# 2022_EDA.net
KiCad netlist of a schematic drawn in EasyEDA Pro
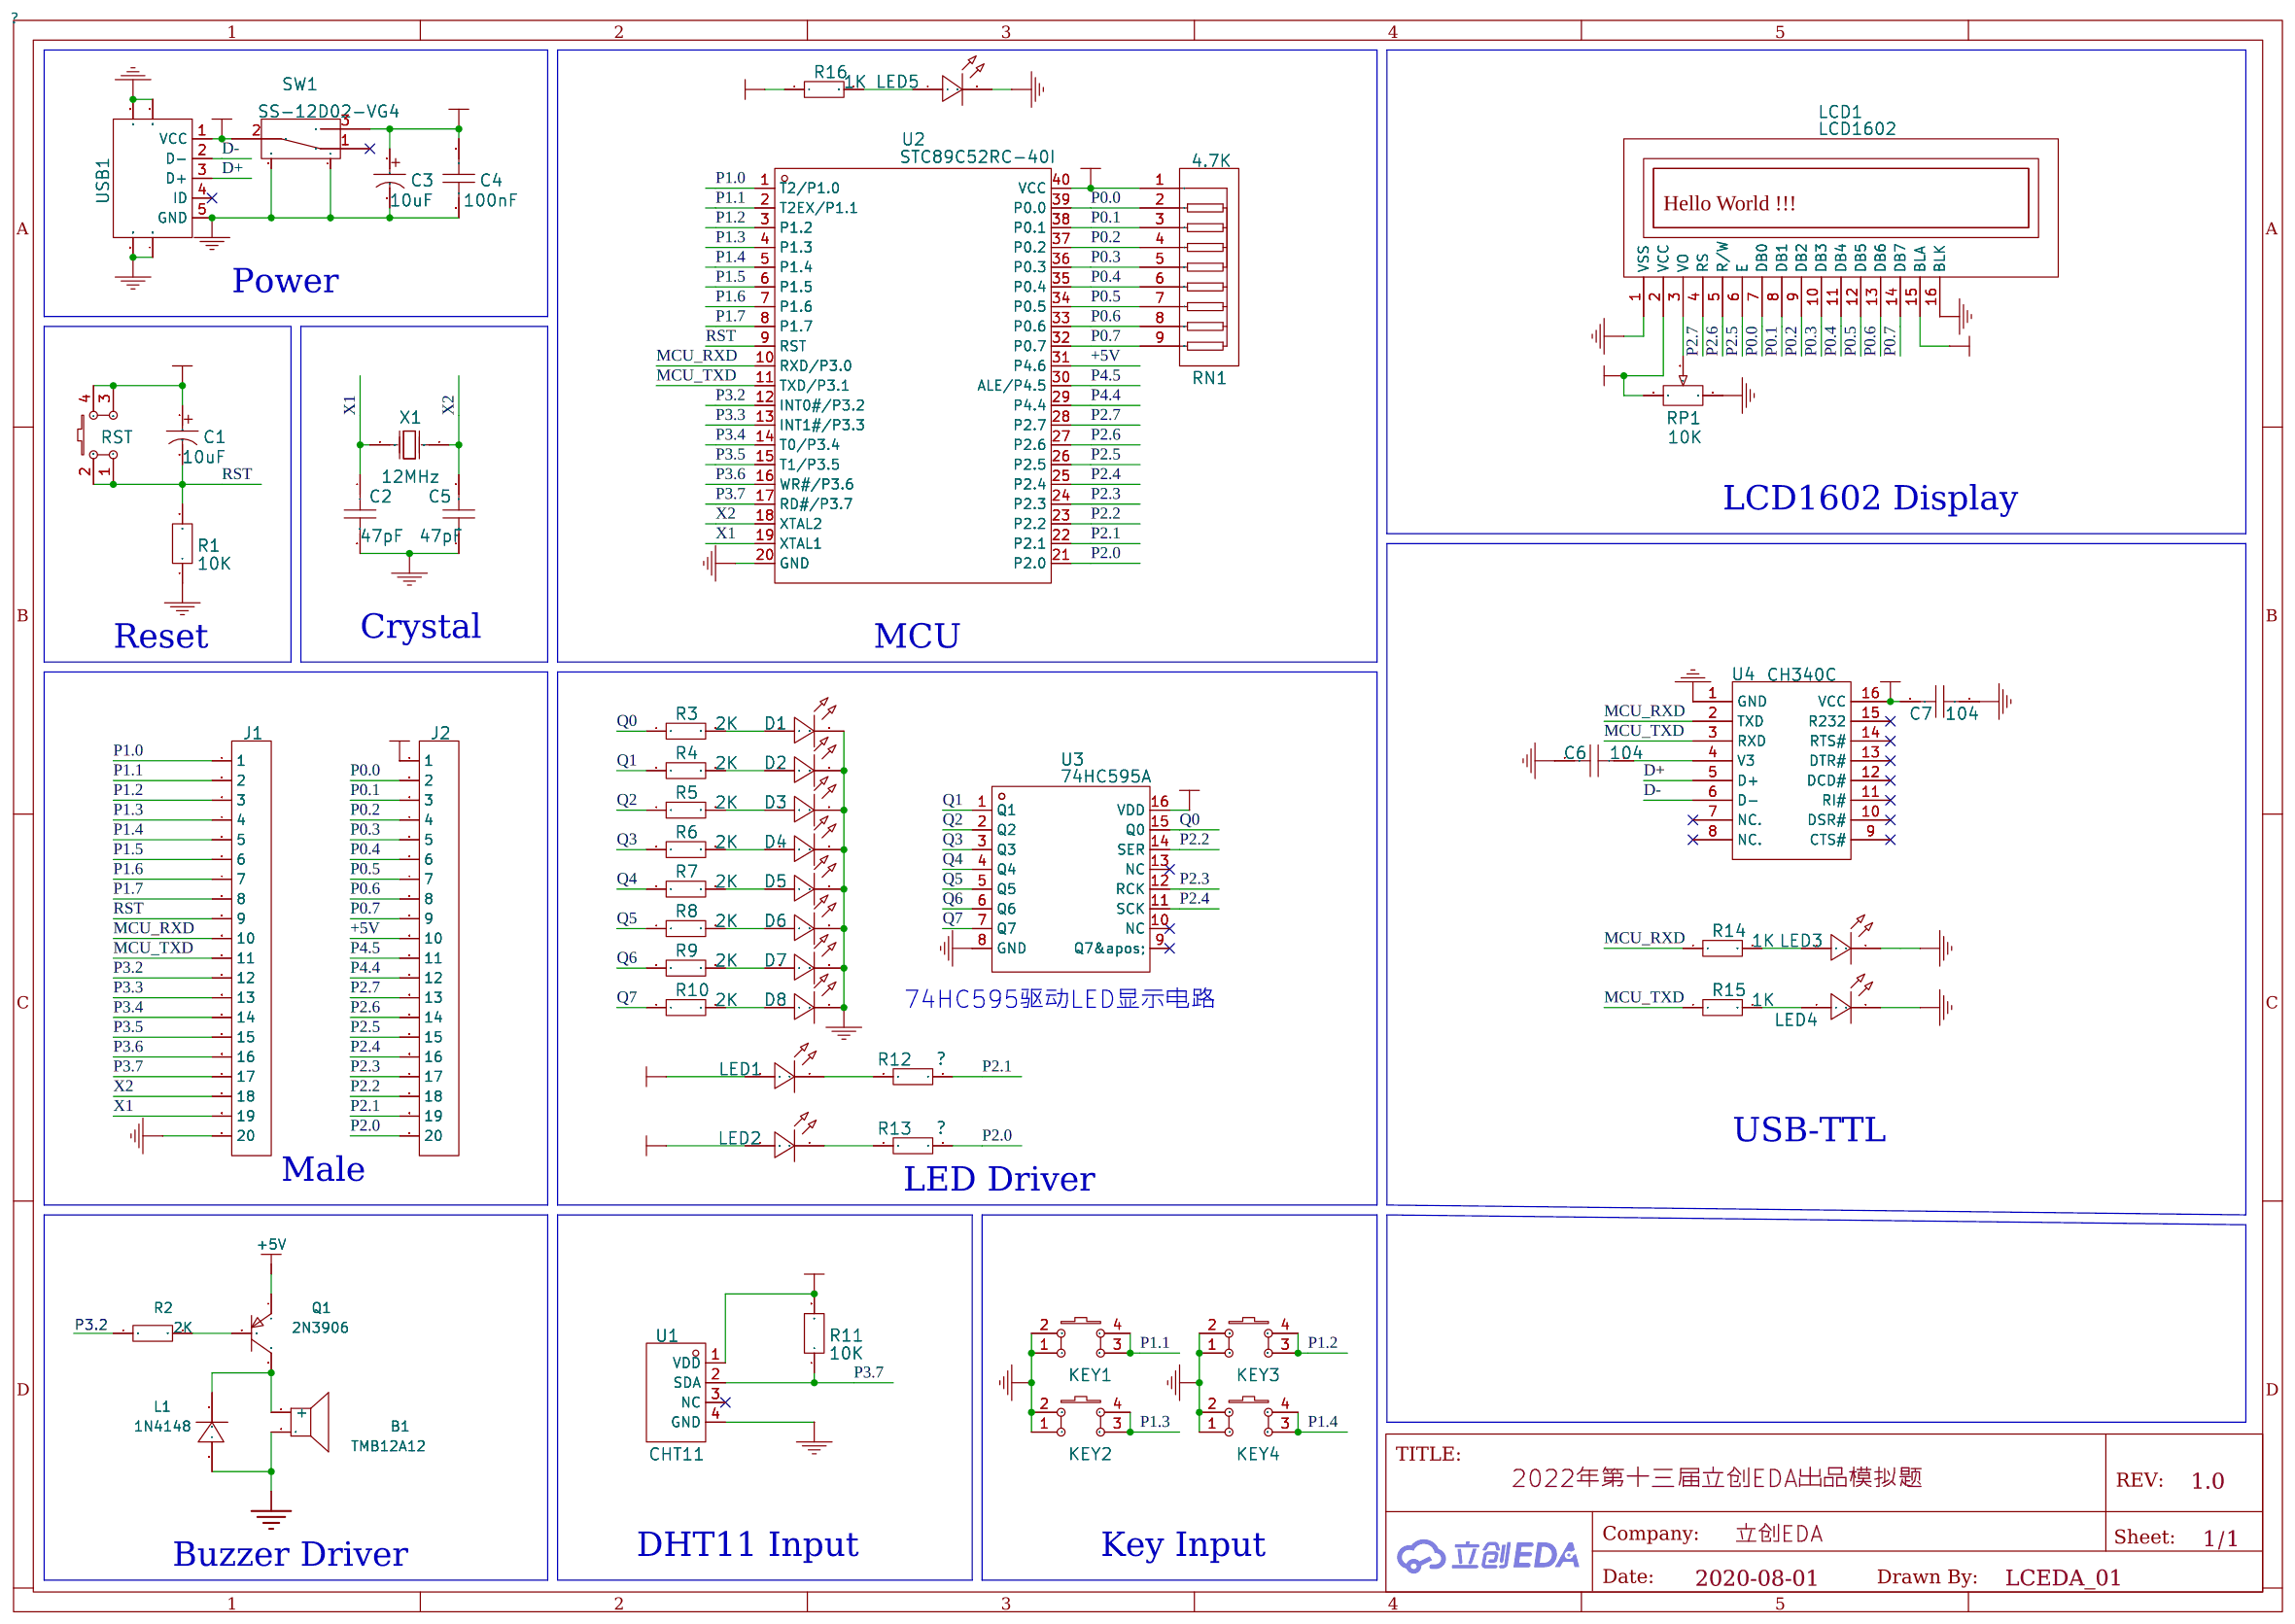
[diagram p0: schematic sheet]

(export (version "E")
  (design (tool "Eeschema 10.0.6"))
  (components
    (comp (ref "B1") (value "TMB12A12") (libsource (lib "easyedapro") (part "TMB12A12")))
    (comp (ref "C1")
      (value "10uF")
      (fields (field (name "Manufacturer Part") "10uF 25V 5*11") (field (name "Manufacturer") "ValuePro"))
      (libsource (lib "easyedapro") (part "10uF"))
    )
    (comp (ref "C2")
      (value "47pF")
      (fields
        (field (name "Manufacturer Part") "CC81-N5S2L1B470KSE")
        (field (name "Manufacturer") "Guangdong Fenghua Advanced Tech")
      )
      (libsource (lib "easyedapro") (part "47pF"))
    )
    (comp (ref "C3")
      (value "10uF")
      (fields (field (name "Manufacturer Part") "10uF 25V 5*11") (field (name "Manufacturer") "ValuePro"))
      (libsource (lib "easyedapro") (part "10uF"))
    )
    (comp (ref "C4")
      (value "100nF")
      (fields
        (field (name "Manufacturer Part") "CC1H104ZA1FD3F5O10MF")
        (field (name "Manufacturer") "Dersonic")
      )
      (libsource (lib "easyedapro") (part "104"))
    )
    (comp (ref "C5")
      (value "47pF")
      (fields
        (field (name "Manufacturer Part") "CC81-N5S2L1B470KSE")
        (field (name "Manufacturer") "Guangdong Fenghua Advanced Tech")
      )
      (libsource (lib "easyedapro") (part "47pF"))
    )
    (comp (ref "C6")
      (value "104")
      (fields
        (field (name "Manufacturer Part") "CC1H104ZA1FD3F5O10MF")
        (field (name "Manufacturer") "Dersonic")
      )
      (libsource (lib "easyedapro") (part "104"))
    )
    (comp (ref "C7")
      (value "104")
      (fields
        (field (name "Manufacturer Part") "CC1H104ZA1FD3F5O10MF")
        (field (name "Manufacturer") "Dersonic")
      )
      (libsource (lib "easyedapro") (part "104"))
    )
    (comp (ref "D1")
      (value "LED-0805_B")
      (fields (field (name "Manufacturer Part") "D-B080508B1-KS2") (field (name "Manufacturer") "方舟 ARKLED"))
      (libsource (lib "easyedapro") (part "LED-0805_B"))
    )
    (comp (ref "D2")
      (value "LED-0805_B")
      (fields (field (name "Manufacturer Part") "D-B080508B1-KS2") (field (name "Manufacturer") "方舟 ARKLED"))
      (libsource (lib "easyedapro") (part "LED-0805_B"))
    )
    (comp (ref "D3")
      (value "LED-0805_B")
      (fields (field (name "Manufacturer Part") "D-B080508B1-KS2") (field (name "Manufacturer") "方舟 ARKLED"))
      (libsource (lib "easyedapro") (part "LED-0805_B"))
    )
    (comp (ref "D4")
      (value "LED-0805_B")
      (fields (field (name "Manufacturer Part") "D-B080508B1-KS2") (field (name "Manufacturer") "方舟 ARKLED"))
      (libsource (lib "easyedapro") (part "LED-0805_B"))
    )
    (comp (ref "D5")
      (value "LED-0805_B")
      (fields (field (name "Manufacturer Part") "D-B080508B1-KS2") (field (name "Manufacturer") "方舟 ARKLED"))
      (libsource (lib "easyedapro") (part "LED-0805_B"))
    )
    (comp (ref "D6")
      (value "LED-0805_B")
      (fields (field (name "Manufacturer Part") "D-B080508B1-KS2") (field (name "Manufacturer") "方舟 ARKLED"))
      (libsource (lib "easyedapro") (part "LED-0805_B"))
    )
    (comp (ref "D7")
      (value "LED-0805_B")
      (fields (field (name "Manufacturer Part") "D-B080508B1-KS2") (field (name "Manufacturer") "方舟 ARKLED"))
      (libsource (lib "easyedapro") (part "LED-0805_B"))
    )
    (comp (ref "D8")
      (value "LED-0805_B")
      (fields (field (name "Manufacturer Part") "D-B080508B1-KS2") (field (name "Manufacturer") "方舟 ARKLED"))
      (libsource (lib "easyedapro") (part "LED-0805_B"))
    )
    (comp (ref "J1") (value "HDR-M-2.54_1x20") (libsource (lib "easyedapro") (part "HDR-M-2.54_1x20")))
    (comp (ref "J2") (value "HDR-M-2.54_1x20") (libsource (lib "easyedapro") (part "HDR-M-2.54_1x20")))
    (comp (ref "KEY1")
      (value "K4-6×6_SMD")
      (fields (field (name "Manufacturer Part") "K2-6639SP-D4SC-04") (field (name "Manufacturer") "韩国韩荣"))
      (libsource (lib "easyedapro") (part "K4-6×6_SMD"))
    )
    (comp (ref "KEY2")
      (value "K4-6×6_SMD")
      (fields (field (name "Manufacturer Part") "K2-6639SP-D4SC-04") (field (name "Manufacturer") "韩国韩荣"))
      (libsource (lib "easyedapro") (part "K4-6×6_SMD"))
    )
    (comp (ref "KEY3")
      (value "K4-6×6_SMD")
      (fields (field (name "Manufacturer Part") "K2-6639SP-D4SC-04") (field (name "Manufacturer") "韩国韩荣"))
      (libsource (lib "easyedapro") (part "K4-6×6_SMD"))
    )
    (comp (ref "KEY4")
      (value "K4-6×6_SMD")
      (fields (field (name "Manufacturer Part") "K2-6639SP-D4SC-04") (field (name "Manufacturer") "韩国韩荣"))
      (libsource (lib "easyedapro") (part "K4-6×6_SMD"))
    )
    (comp (ref "L1") (value "1N4148") (libsource (lib "easyedapro") (part "1N4148")))
    (comp (ref "LCD1")
      (value "LCD1602")
      (fields
        (field (name "Manufacturer Part") "LCM1602K-NSW-BBW")
        (field (name "Manufacturer") "LONTECH(厦门龙特)")
      )
      (libsource (lib "easyedapro") (part "LCD1602"))
    )
    (comp (ref "LED1")
      (value "LED-TH-3mm_B")
      (fields
        (field (name "Manufacturer Part") "204-10SUBC/S400-A4")
        (field (name "Manufacturer") "EVERLIGHT(台湾亿光)")
      )
      (libsource (lib "easyedapro") (part "LED-TH-3mm_B"))
    )
    (comp (ref "LED2")
      (value "LED-TH-3mm_G")
      (fields
        (field (name "Manufacturer Part") "204-10SYGD/S530-E3")
        (field (name "Manufacturer") "EVERLIGHT(台湾亿光)")
      )
      (libsource (lib "easyedapro") (part "LED-TH-3mm_G"))
    )
    (comp (ref "LED3")
      (value "LED-0805_B")
      (fields (field (name "Manufacturer Part") "D-B080508B1-KS2") (field (name "Manufacturer") "方舟 ARKLED"))
      (libsource (lib "easyedapro") (part "LED-0805_B"))
    )
    (comp (ref "LED4")
      (value "LED-0805_G")
      (fields (field (name "Manufacturer Part") "NCD0805G1") (field (name "Manufacturer") "国星光电"))
      (libsource (lib "easyedapro") (part "LED-0805_G"))
    )
    (comp (ref "LED5")
      (value "LED-TH-3mm_R")
      (fields
        (field (name "Manufacturer Part") "204-10SDRD/S530-A3-L")
        (field (name "Manufacturer") "EVERLIGHT(台湾亿光)")
      )
      (libsource (lib "easyedapro") (part "LED-TH-3mm_R"))
    )
    (comp (ref "Q1") (value "2N3906") (libsource (lib "easyedapro") (part "2N3906")))
    (comp (ref "R1")
      (value "10K")
      (fields (field (name "Manufacturer Part") "RN 1/4W 10K F T/B A1") (field (name "Manufacturer") "TyoHM"))
      (libsource (lib "") (part "10K_1"))
    )
    (comp (ref "R2") (value "2K") (libsource (lib "") (part "2K_1")))
    (comp (ref "R3")
      (value "2K")
      (fields (field (name "Manufacturer Part") "ARG05FTC2001") (field (name "Manufacturer") "Viking Tech"))
      (libsource (lib "easyedapro") (part "2K"))
    )
    (comp (ref "R4")
      (value "2K")
      (fields (field (name "Manufacturer Part") "ARG05FTC2001") (field (name "Manufacturer") "Viking Tech"))
      (libsource (lib "easyedapro") (part "2K"))
    )
    (comp (ref "R5")
      (value "2K")
      (fields (field (name "Manufacturer Part") "ARG05FTC2001") (field (name "Manufacturer") "Viking Tech"))
      (libsource (lib "easyedapro") (part "2K"))
    )
    (comp (ref "R6")
      (value "2K")
      (fields (field (name "Manufacturer Part") "ARG05FTC2001") (field (name "Manufacturer") "Viking Tech"))
      (libsource (lib "easyedapro") (part "2K"))
    )
    (comp (ref "R7")
      (value "2K")
      (fields (field (name "Manufacturer Part") "ARG05FTC2001") (field (name "Manufacturer") "Viking Tech"))
      (libsource (lib "easyedapro") (part "2K"))
    )
    (comp (ref "R8")
      (value "2K")
      (fields (field (name "Manufacturer Part") "ARG05FTC2001") (field (name "Manufacturer") "Viking Tech"))
      (libsource (lib "easyedapro") (part "2K"))
    )
    (comp (ref "R9")
      (value "2K")
      (fields (field (name "Manufacturer Part") "ARG05FTC2001") (field (name "Manufacturer") "Viking Tech"))
      (libsource (lib "easyedapro") (part "2K"))
    )
    (comp (ref "R10")
      (value "2K")
      (fields (field (name "Manufacturer Part") "ARG05FTC2001") (field (name "Manufacturer") "Viking Tech"))
      (libsource (lib "easyedapro") (part "2K"))
    )
    (comp (ref "R11")
      (value "10K")
      (fields (field (name "Manufacturer Part") "RN 1/4W 10K F T/B A1") (field (name "Manufacturer") "TyoHM"))
      (libsource (lib "") (part "10K_1"))
    )
    (comp (ref "R12")
      (value "？")
      (fields (field (name "Manufacturer Part") "RN1/2WS2KΩFT/BA1") (field (name "Manufacturer") "TyoHM"))
      (libsource (lib "easyedapro") (part "？"))
    )
    (comp (ref "R13")
      (value "？")
      (fields (field (name "Manufacturer Part") "RN1/2WS2KΩFT/BA1") (field (name "Manufacturer") "TyoHM"))
      (libsource (lib "easyedapro") (part "？"))
    )
    (comp (ref "R14")
      (value "1K")
      (fields (field (name "Manufacturer Part") "ARG05FTC2001") (field (name "Manufacturer") "Viking Tech"))
      (libsource (lib "easyedapro") (part "2K"))
    )
    (comp (ref "R15")
      (value "1K")
      (fields (field (name "Manufacturer Part") "ARG05FTC2001") (field (name "Manufacturer") "Viking Tech"))
      (libsource (lib "easyedapro") (part "2K"))
    )
    (comp (ref "R16")
      (value "1K")
      (fields (field (name "Manufacturer Part") "RN1/2WS2KΩFT/BA1") (field (name "Manufacturer") "TyoHM"))
      (libsource (lib "easyedapro") (part "？"))
    )
    (comp (ref "RN1")
      (value "4.7K")
      (fields (field (name "Manufacturer Part") "A09-472JP") (field (name "Manufacturer") "FH"))
      (libsource (lib "easyedapro") (part "4.7K"))
    )
    (comp (ref "RP1") (value "10K") (libsource (lib "easyedapro") (part "10K")))
    (comp (ref "RST")
      (value "K4-6×6_SMD")
      (fields (field (name "Manufacturer Part") "K2-6639SP-D4SC-04") (field (name "Manufacturer") "韩国韩荣"))
      (libsource (lib "easyedapro") (part "K4-6×6_SMD"))
    )
    (comp (ref "SW1")
      (value "SS-12D02-VG4")
      (fields (field (name "Manufacturer") "Rectangular Connectors - Contacts"))
      (libsource (lib "easyedapro") (part "SS-12D02-VG4"))
    )
    (comp (ref "U1")
      (value "CHT11")
      (fields (field (name "Manufacturer") "CYBERSEN"))
      (libsource (lib "easyedapro") (part "CHT11"))
    )
    (comp (ref "U2")
      (value "STC89C52RC-40I")
      (fields (field (name "Manufacturer") "STC"))
      (libsource (lib "easyedapro") (part "STC89C52RC-40I"))
    )
    (comp (ref "U3")
      (value "74HC595A")
      (fields (field (name "Manufacturer") "FM"))
      (libsource (lib "easyedapro") (part "74HC595A"))
    )
    (comp (ref "U4")
      (value "CH340C")
      (fields (field (name "Manufacturer") "WCH"))
      (libsource (lib "easyedapro") (part "CH340C"))
    )
    (comp (ref "USB1")
      (value "USB-Micro_2")
      (fields (field (name "Manufacturer") "ValuePro"))
      (libsource (lib "easyedapro") (part "USB-Micro_2"))
    )
    (comp (ref "X1")
      (value "12MHz")
      (fields
        (field (name "Manufacturer Part") "B12000J233")
        (field (name "Manufacturer") "ZheJiang East Crystal Elec")
      )
      (libsource (lib "easyedapro") (part "12MHz"))
    )
  )
  (nets
    (net (code "1") (name "+5V") (class "Default")
      (node (ref "C1") (pin "1") (pinfunction "1_1") (pintype "input"))
      (node (ref "C3") (pin "1") (pinfunction "1_1") (pintype "input"))
      (node (ref "C4") (pin "2") (pinfunction "2_2") (pintype "input"))
      (node (ref "J2") (pin "1") (pinfunction "1_1") (pintype "input"))
      (node (ref "J2") (pin "10") (pinfunction "10_10") (pintype "input"))
      (node (ref "LCD1") (pin "15") (pinfunction "BLA_15") (pintype "input"))
      (node (ref "LCD1") (pin "2") (pinfunction "VCC_2") (pintype "input"))
      (node (ref "LED1") (pin "1") (pinfunction "1_1") (pintype "input"))
      (node (ref "LED2") (pin "1") (pinfunction "1_1") (pintype "input"))
      (node (ref "Q1") (pin "1") (pinfunction "E_1") (pintype "input"))
      (node (ref "R11") (pin "2") (pinfunction "2_2") (pintype "input"))
      (node (ref "R16") (pin "1") (pinfunction "1_1") (pintype "input"))
      (node (ref "RN1") (pin "1") (pinfunction "1_1") (pintype "input"))
      (node (ref "RP1") (pin "1") (pinfunction "1_1") (pintype "input"))
      (node (ref "RST") (pin "3") (pinfunction "3_3") (pintype "input"))
      (node (ref "RST") (pin "4") (pinfunction "4_4") (pintype "input"))
      (node (ref "SW1") (pin "3") (pinfunction "3_3") (pintype "input"))
      (node (ref "U1") (pin "1") (pinfunction "VDD_1") (pintype "input"))
      (node (ref "U2") (pin "31") (pinfunction "P4.6_31") (pintype "input"))
      (node (ref "U2") (pin "40") (pinfunction "VCC_40") (pintype "input"))
      (node (ref "U3") (pin "16") (pinfunction "VDD_16") (pintype "input"))
    )
    (net (code "2") (name "/D+") (class "Default")
      (node (ref "U4") (pin "5") (pinfunction "D+_5") (pintype "input"))
      (node (ref "USB1") (pin "3") (pinfunction "D+_3") (pintype "input"))
    )
    (net (code "3") (name "/D-") (class "Default")
      (node (ref "U4") (pin "6") (pinfunction "D-_6") (pintype "input"))
      (node (ref "USB1") (pin "2") (pinfunction "D-_2") (pintype "input"))
    )
    (net (code "4") (name "/MCU_RXD") (class "Default")
      (node (ref "J1") (pin "10") (pinfunction "10_10") (pintype "input"))
      (node (ref "R14") (pin "1") (pinfunction "1_1") (pintype "input"))
      (node (ref "U2") (pin "10") (pinfunction "RXD/P3.0_10") (pintype "input"))
      (node (ref "U4") (pin "2") (pinfunction "TXD_2") (pintype "input"))
    )
    (net (code "5") (name "/MCU_TXD") (class "Default")
      (node (ref "J1") (pin "11") (pinfunction "11_11") (pintype "input"))
      (node (ref "R15") (pin "1") (pinfunction "1_1") (pintype "input"))
      (node (ref "U2") (pin "11") (pinfunction "TXD/P3.1_11") (pintype "input"))
      (node (ref "U4") (pin "3") (pinfunction "RXD_3") (pintype "input"))
    )
    (net (code "6") (name "/P0.0") (class "Default")
      (node (ref "J2") (pin "2") (pinfunction "2_2") (pintype "input"))
      (node (ref "LCD1") (pin "7") (pinfunction "DB0_7") (pintype "input"))
      (node (ref "RN1") (pin "2") (pinfunction "2_2") (pintype "input"))
      (node (ref "U2") (pin "39") (pinfunction "P0.0_39") (pintype "input"))
    )
    (net (code "7") (name "/P0.1") (class "Default")
      (node (ref "J2") (pin "3") (pinfunction "3_3") (pintype "input"))
      (node (ref "LCD1") (pin "8") (pinfunction "DB1_8") (pintype "input"))
      (node (ref "RN1") (pin "3") (pinfunction "3_3") (pintype "input"))
      (node (ref "U2") (pin "38") (pinfunction "P0.1_38") (pintype "input"))
    )
    (net (code "8") (name "/P0.2") (class "Default")
      (node (ref "J2") (pin "4") (pinfunction "4_4") (pintype "input"))
      (node (ref "LCD1") (pin "9") (pinfunction "DB2_9") (pintype "input"))
      (node (ref "RN1") (pin "4") (pinfunction "4_4") (pintype "input"))
      (node (ref "U2") (pin "37") (pinfunction "P0.2_37") (pintype "input"))
    )
    (net (code "9") (name "/P0.3") (class "Default")
      (node (ref "J2") (pin "5") (pinfunction "5_5") (pintype "input"))
      (node (ref "LCD1") (pin "10") (pinfunction "DB3_10") (pintype "input"))
      (node (ref "RN1") (pin "5") (pinfunction "5_5") (pintype "input"))
      (node (ref "U2") (pin "36") (pinfunction "P0.3_36") (pintype "input"))
    )
    (net (code "10") (name "/P0.4") (class "Default")
      (node (ref "J2") (pin "6") (pinfunction "6_6") (pintype "input"))
      (node (ref "LCD1") (pin "11") (pinfunction "DB4_11") (pintype "input"))
      (node (ref "RN1") (pin "6") (pinfunction "6_6") (pintype "input"))
      (node (ref "U2") (pin "35") (pinfunction "P0.4_35") (pintype "input"))
    )
    (net (code "11") (name "/P0.5") (class "Default")
      (node (ref "J2") (pin "7") (pinfunction "7_7") (pintype "input"))
      (node (ref "LCD1") (pin "12") (pinfunction "DB5_12") (pintype "input"))
      (node (ref "RN1") (pin "7") (pinfunction "7_7") (pintype "input"))
      (node (ref "U2") (pin "34") (pinfunction "P0.5_34") (pintype "input"))
    )
    (net (code "12") (name "/P0.6") (class "Default")
      (node (ref "J2") (pin "8") (pinfunction "8_8") (pintype "input"))
      (node (ref "LCD1") (pin "13") (pinfunction "DB6_13") (pintype "input"))
      (node (ref "RN1") (pin "8") (pinfunction "8_8") (pintype "input"))
      (node (ref "U2") (pin "33") (pinfunction "P0.6_33") (pintype "input"))
    )
    (net (code "13") (name "/P0.7") (class "Default")
      (node (ref "J2") (pin "9") (pinfunction "9_9") (pintype "input"))
      (node (ref "LCD1") (pin "14") (pinfunction "DB7_14") (pintype "input"))
      (node (ref "RN1") (pin "9") (pinfunction "9_9") (pintype "input"))
      (node (ref "U2") (pin "32") (pinfunction "P0.7_32") (pintype "input"))
    )
    (net (code "14") (name "/P1.0") (class "Default")
      (node (ref "J1") (pin "1") (pinfunction "1_1") (pintype "input"))
      (node (ref "U2") (pin "1") (pinfunction "T2/P1.0_1") (pintype "input"))
    )
    (net (code "15") (name "/P1.1") (class "Default")
      (node (ref "J1") (pin "2") (pinfunction "2_2") (pintype "input"))
      (node (ref "KEY1") (pin "3") (pinfunction "3_3") (pintype "input"))
      (node (ref "KEY1") (pin "4") (pinfunction "4_4") (pintype "input"))
      (node (ref "U2") (pin "2") (pinfunction "T2EX/P1.1_2") (pintype "input"))
    )
    (net (code "16") (name "/P1.2") (class "Default")
      (node (ref "J1") (pin "3") (pinfunction "3_3") (pintype "input"))
      (node (ref "KEY3") (pin "3") (pinfunction "3_3") (pintype "input"))
      (node (ref "KEY3") (pin "4") (pinfunction "4_4") (pintype "input"))
      (node (ref "U2") (pin "3") (pinfunction "P1.2_3") (pintype "input"))
    )
    (net (code "17") (name "/P1.3") (class "Default")
      (node (ref "J1") (pin "4") (pinfunction "4_4") (pintype "input"))
      (node (ref "KEY2") (pin "3") (pinfunction "3_3") (pintype "input"))
      (node (ref "KEY2") (pin "4") (pinfunction "4_4") (pintype "input"))
      (node (ref "U2") (pin "4") (pinfunction "P1.3_4") (pintype "input"))
    )
    (net (code "18") (name "/P1.4") (class "Default")
      (node (ref "J1") (pin "5") (pinfunction "5_5") (pintype "input"))
      (node (ref "KEY4") (pin "3") (pinfunction "3_3") (pintype "input"))
      (node (ref "KEY4") (pin "4") (pinfunction "4_4") (pintype "input"))
      (node (ref "U2") (pin "5") (pinfunction "P1.4_5") (pintype "input"))
    )
    (net (code "19") (name "/P1.5") (class "Default")
      (node (ref "J1") (pin "6") (pinfunction "6_6") (pintype "input"))
      (node (ref "U2") (pin "6") (pinfunction "P1.5_6") (pintype "input"))
    )
    (net (code "20") (name "/P1.6") (class "Default")
      (node (ref "J1") (pin "7") (pinfunction "7_7") (pintype "input"))
      (node (ref "U2") (pin "7") (pinfunction "P1.6_7") (pintype "input"))
    )
    (net (code "21") (name "/P1.7") (class "Default")
      (node (ref "J1") (pin "8") (pinfunction "8_8") (pintype "input"))
      (node (ref "U2") (pin "8") (pinfunction "P1.7_8") (pintype "input"))
    )
    (net (code "22") (name "/P2.0") (class "Default")
      (node (ref "J2") (pin "20") (pinfunction "20_20") (pintype "input"))
      (node (ref "R13") (pin "2") (pinfunction "2_2") (pintype "input"))
      (node (ref "U2") (pin "21") (pinfunction "P2.0_21") (pintype "input"))
    )
    (net (code "23") (name "/P2.1") (class "Default")
      (node (ref "J2") (pin "19") (pinfunction "19_19") (pintype "input"))
      (node (ref "R12") (pin "2") (pinfunction "2_2") (pintype "input"))
      (node (ref "U2") (pin "22") (pinfunction "P2.1_22") (pintype "input"))
    )
    (net (code "24") (name "/P2.2") (class "Default")
      (node (ref "J2") (pin "18") (pinfunction "18_18") (pintype "input"))
      (node (ref "U2") (pin "23") (pinfunction "P2.2_23") (pintype "input"))
      (node (ref "U3") (pin "14") (pinfunction "SER_14") (pintype "input"))
    )
    (net (code "25") (name "/P2.3") (class "Default")
      (node (ref "J2") (pin "17") (pinfunction "17_17") (pintype "input"))
      (node (ref "U2") (pin "24") (pinfunction "P2.3_24") (pintype "input"))
      (node (ref "U3") (pin "12") (pinfunction "RCK_12") (pintype "input"))
    )
    (net (code "26") (name "/P2.4") (class "Default")
      (node (ref "J2") (pin "16") (pinfunction "16_16") (pintype "input"))
      (node (ref "U2") (pin "25") (pinfunction "P2.4_25") (pintype "input"))
      (node (ref "U3") (pin "11") (pinfunction "SCK_11") (pintype "input"))
    )
    (net (code "27") (name "/P2.5") (class "Default")
      (node (ref "J2") (pin "15") (pinfunction "15_15") (pintype "input"))
      (node (ref "LCD1") (pin "6") (pinfunction "E_6") (pintype "input"))
      (node (ref "U2") (pin "26") (pinfunction "P2.5_26") (pintype "input"))
    )
    (net (code "28") (name "/P2.6") (class "Default")
      (node (ref "J2") (pin "14") (pinfunction "14_14") (pintype "input"))
      (node (ref "LCD1") (pin "5") (pinfunction "R/W_5") (pintype "input"))
      (node (ref "U2") (pin "27") (pinfunction "P2.6_27") (pintype "input"))
    )
    (net (code "29") (name "/P2.7") (class "Default")
      (node (ref "J2") (pin "13") (pinfunction "13_13") (pintype "input"))
      (node (ref "LCD1") (pin "4") (pinfunction "RS_4") (pintype "input"))
      (node (ref "U2") (pin "28") (pinfunction "P2.7_28") (pintype "input"))
    )
    (net (code "30") (name "/P3.2") (class "Default")
      (node (ref "J1") (pin "12") (pinfunction "12_12") (pintype "input"))
      (node (ref "R2") (pin "1") (pinfunction "1_1") (pintype "input"))
      (node (ref "U2") (pin "12") (pinfunction "INT0#/P3.2_12") (pintype "input"))
    )
    (net (code "31") (name "/P3.3") (class "Default")
      (node (ref "J1") (pin "13") (pinfunction "13_13") (pintype "input"))
      (node (ref "U2") (pin "13") (pinfunction "INT1#/P3.3_13") (pintype "input"))
    )
    (net (code "32") (name "/P3.4") (class "Default")
      (node (ref "J1") (pin "14") (pinfunction "14_14") (pintype "input"))
      (node (ref "U2") (pin "14") (pinfunction "T0/P3.4_14") (pintype "input"))
    )
    (net (code "33") (name "/P3.5") (class "Default")
      (node (ref "J1") (pin "15") (pinfunction "15_15") (pintype "input"))
      (node (ref "U2") (pin "15") (pinfunction "T1/P3.5_15") (pintype "input"))
    )
    (net (code "34") (name "/P3.6") (class "Default")
      (node (ref "J1") (pin "16") (pinfunction "16_16") (pintype "input"))
      (node (ref "U2") (pin "16") (pinfunction "WR#/P3.6_16") (pintype "input"))
    )
    (net (code "35") (name "/P3.7") (class "Default")
      (node (ref "J1") (pin "17") (pinfunction "17_17") (pintype "input"))
      (node (ref "R11") (pin "1") (pinfunction "1_1") (pintype "input"))
      (node (ref "U1") (pin "2") (pinfunction "SDA_2") (pintype "input"))
      (node (ref "U2") (pin "17") (pinfunction "RD#/P3.7_17") (pintype "input"))
    )
    (net (code "36") (name "/P4.4") (class "Default")
      (node (ref "J2") (pin "12") (pinfunction "12_12") (pintype "input"))
      (node (ref "U2") (pin "29") (pinfunction "P4.4_29") (pintype "input"))
    )
    (net (code "37") (name "/P4.5") (class "Default")
      (node (ref "J2") (pin "11") (pinfunction "11_11") (pintype "input"))
      (node (ref "U2") (pin "30") (pinfunction "ALE/P4.5_30") (pintype "input"))
    )
    (net (code "38") (name "/Q0") (class "Default")
      (node (ref "R3") (pin "1") (pinfunction "1_1") (pintype "input"))
      (node (ref "U3") (pin "15") (pinfunction "Q0_15") (pintype "input"))
    )
    (net (code "39") (name "/Q1") (class "Default")
      (node (ref "R4") (pin "1") (pinfunction "1_1") (pintype "input"))
      (node (ref "U3") (pin "1") (pinfunction "Q1_1") (pintype "input"))
    )
    (net (code "40") (name "/Q2") (class "Default")
      (node (ref "R5") (pin "1") (pinfunction "1_1") (pintype "input"))
      (node (ref "U3") (pin "2") (pinfunction "Q2_2") (pintype "input"))
    )
    (net (code "41") (name "/Q3") (class "Default")
      (node (ref "R6") (pin "1") (pinfunction "1_1") (pintype "input"))
      (node (ref "U3") (pin "3") (pinfunction "Q3_3") (pintype "input"))
    )
    (net (code "42") (name "/Q4") (class "Default")
      (node (ref "R7") (pin "1") (pinfunction "1_1") (pintype "input"))
      (node (ref "U3") (pin "4") (pinfunction "Q4_4") (pintype "input"))
    )
    (net (code "43") (name "/Q5") (class "Default")
      (node (ref "R8") (pin "1") (pinfunction "1_1") (pintype "input"))
      (node (ref "U3") (pin "5") (pinfunction "Q5_5") (pintype "input"))
    )
    (net (code "44") (name "/Q6") (class "Default")
      (node (ref "R9") (pin "1") (pinfunction "1_1") (pintype "input"))
      (node (ref "U3") (pin "6") (pinfunction "Q6_6") (pintype "input"))
    )
    (net (code "45") (name "/Q7") (class "Default")
      (node (ref "R10") (pin "1") (pinfunction "1_1") (pintype "input"))
      (node (ref "U3") (pin "7") (pinfunction "Q7_7") (pintype "input"))
    )
    (net (code "46") (name "/RST") (class "Default")
      (node (ref "C1") (pin "2") (pinfunction "2_2") (pintype "input"))
      (node (ref "J1") (pin "9") (pinfunction "9_9") (pintype "input"))
      (node (ref "R1") (pin "2") (pinfunction "2_2") (pintype "input"))
      (node (ref "RST") (pin "1") (pinfunction "1_1") (pintype "input"))
      (node (ref "RST") (pin "2") (pinfunction "2_2") (pintype "input"))
      (node (ref "U2") (pin "9") (pinfunction "RST_9") (pintype "input"))
    )
    (net (code "47") (name "/X1") (class "Default")
      (node (ref "C2") (pin "1") (pinfunction "1_1") (pintype "input"))
      (node (ref "J1") (pin "19") (pinfunction "19_19") (pintype "input"))
      (node (ref "U2") (pin "19") (pinfunction "XTAL1_19") (pintype "input"))
      (node (ref "X1") (pin "2") (pinfunction "OSC2_2") (pintype "input"))
    )
    (net (code "48") (name "/X2") (class "Default")
      (node (ref "C5") (pin "2") (pinfunction "2_2") (pintype "input"))
      (node (ref "J1") (pin "18") (pinfunction "18_18") (pintype "input"))
      (node (ref "U2") (pin "18") (pinfunction "XTAL2_18") (pintype "input"))
      (node (ref "X1") (pin "1") (pinfunction "OSC1_1") (pintype "input"))
    )
    (net (code "49") (name "GND") (class "Default")
      (node (ref "B1") (pin "2") (pinfunction "2_2") (pintype "input"))
      (node (ref "C2") (pin "2") (pinfunction "2_2") (pintype "input"))
      (node (ref "C3") (pin "2") (pinfunction "2_2") (pintype "input"))
      (node (ref "C4") (pin "1") (pinfunction "1_1") (pintype "input"))
      (node (ref "C5") (pin "1") (pinfunction "1_1") (pintype "input"))
      (node (ref "C6") (pin "2") (pinfunction "2_2") (pintype "input"))
      (node (ref "C7") (pin "1") (pinfunction "1_1") (pintype "input"))
      (node (ref "D1") (pin "2") (pinfunction "2_2") (pintype "input"))
      (node (ref "D2") (pin "2") (pinfunction "2_2") (pintype "input"))
      (node (ref "D3") (pin "2") (pinfunction "2_2") (pintype "input"))
      (node (ref "D4") (pin "2") (pinfunction "2_2") (pintype "input"))
      (node (ref "D5") (pin "2") (pinfunction "2_2") (pintype "input"))
      (node (ref "D6") (pin "2") (pinfunction "2_2") (pintype "input"))
      (node (ref "D7") (pin "2") (pinfunction "2_2") (pintype "input"))
      (node (ref "D8") (pin "2") (pinfunction "2_2") (pintype "input"))
      (node (ref "J1") (pin "20") (pinfunction "20_20") (pintype "input"))
      (node (ref "KEY1") (pin "1") (pinfunction "1_1") (pintype "input"))
      (node (ref "KEY1") (pin "2") (pinfunction "2_2") (pintype "input"))
      (node (ref "KEY2") (pin "1") (pinfunction "1_1") (pintype "input"))
      (node (ref "KEY2") (pin "2") (pinfunction "2_2") (pintype "input"))
      (node (ref "KEY3") (pin "1") (pinfunction "1_1") (pintype "input"))
      (node (ref "KEY3") (pin "2") (pinfunction "2_2") (pintype "input"))
      (node (ref "KEY4") (pin "1") (pinfunction "1_1") (pintype "input"))
      (node (ref "KEY4") (pin "2") (pinfunction "2_2") (pintype "input"))
      (node (ref "L1") (pin "1") (pinfunction "A_1") (pintype "input"))
      (node (ref "LCD1") (pin "1") (pinfunction "VSS_1") (pintype "input"))
      (node (ref "LCD1") (pin "16") (pinfunction "BLK_16") (pintype "input"))
      (node (ref "LED3") (pin "2") (pinfunction "2_2") (pintype "input"))
      (node (ref "LED4") (pin "2") (pinfunction "2_2") (pintype "input"))
      (node (ref "LED5") (pin "2") (pinfunction "2_2") (pintype "input"))
      (node (ref "R1") (pin "1") (pinfunction "1_1") (pintype "input"))
      (node (ref "RP1") (pin "3") (pinfunction "3_3") (pintype "input"))
      (node (ref "SW1") (pin "4") (pinfunction "4_4") (pintype "input"))
      (node (ref "SW1") (pin "5") (pinfunction "5_5") (pintype "input"))
      (node (ref "U1") (pin "4") (pinfunction "GND_4") (pintype "input"))
      (node (ref "U2") (pin "20") (pinfunction "GND_20") (pintype "input"))
      (node (ref "U3") (pin "8") (pinfunction "GND_8") (pintype "input"))
      (node (ref "U4") (pin "1") (pinfunction "GND_1") (pintype "input"))
      (node (ref "USB1") (pin "5") (pinfunction "GND_5") (pintype "input"))
      (node (ref "USB1") (pin "6") (pinfunction "SH3_6") (pintype "input"))
      (node (ref "USB1") (pin "7") (pinfunction "SH4_7") (pintype "input"))
      (node (ref "USB1") (pin "8") (pinfunction "SH1_8") (pintype "input"))
      (node (ref "USB1") (pin "9") (pinfunction "SH2_9") (pintype "input"))
    )
    (net (code "50") (name "Net-(B1-+)") (class "Default")
      (node (ref "B1") (pin "1") (pinfunction "+_1") (pintype "input"))
      (node (ref "L1") (pin "2") (pinfunction "C_2") (pintype "input"))
      (node (ref "Q1") (pin "3") (pinfunction "C_3") (pintype "input"))
    )
    (net (code "51") (name "Net-(D1-Pad1)") (class "Default")
      (node (ref "D1") (pin "1") (pinfunction "1_1") (pintype "input"))
      (node (ref "R3") (pin "2") (pinfunction "2_2") (pintype "input"))
    )
    (net (code "52") (name "Net-(D2-Pad1)") (class "Default")
      (node (ref "D2") (pin "1") (pinfunction "1_1") (pintype "input"))
      (node (ref "R4") (pin "2") (pinfunction "2_2") (pintype "input"))
    )
    (net (code "53") (name "Net-(D3-Pad1)") (class "Default")
      (node (ref "D3") (pin "1") (pinfunction "1_1") (pintype "input"))
      (node (ref "R5") (pin "2") (pinfunction "2_2") (pintype "input"))
    )
    (net (code "54") (name "Net-(D4-Pad1)") (class "Default")
      (node (ref "D4") (pin "1") (pinfunction "1_1") (pintype "input"))
      (node (ref "R6") (pin "2") (pinfunction "2_2") (pintype "input"))
    )
    (net (code "55") (name "Net-(D5-Pad1)") (class "Default")
      (node (ref "D5") (pin "1") (pinfunction "1_1") (pintype "input"))
      (node (ref "R7") (pin "2") (pinfunction "2_2") (pintype "input"))
    )
    (net (code "56") (name "Net-(D6-Pad1)") (class "Default")
      (node (ref "D6") (pin "1") (pinfunction "1_1") (pintype "input"))
      (node (ref "R8") (pin "2") (pinfunction "2_2") (pintype "input"))
    )
    (net (code "57") (name "Net-(D7-Pad1)") (class "Default")
      (node (ref "D7") (pin "1") (pinfunction "1_1") (pintype "input"))
      (node (ref "R9") (pin "2") (pinfunction "2_2") (pintype "input"))
    )
    (net (code "58") (name "Net-(D8-Pad1)") (class "Default")
      (node (ref "D8") (pin "1") (pinfunction "1_1") (pintype "input"))
      (node (ref "R10") (pin "2") (pinfunction "2_2") (pintype "input"))
    )
    (net (code "59") (name "Net-(LCD1-VO)") (class "Default")
      (node (ref "LCD1") (pin "3") (pinfunction "VO_3") (pintype "input"))
      (node (ref "RP1") (pin "2") (pinfunction "2_2") (pintype "input"))
    )
    (net (code "60") (name "Net-(LED1-Pad2)") (class "Default")
      (node (ref "LED1") (pin "2") (pinfunction "2_2") (pintype "input"))
      (node (ref "R12") (pin "1") (pinfunction "1_1") (pintype "input"))
    )
    (net (code "61") (name "Net-(LED2-Pad2)") (class "Default")
      (node (ref "LED2") (pin "2") (pinfunction "2_2") (pintype "input"))
      (node (ref "R13") (pin "1") (pinfunction "1_1") (pintype "input"))
    )
    (net (code "62") (name "Net-(LED3-Pad1)") (class "Default")
      (node (ref "LED3") (pin "1") (pinfunction "1_1") (pintype "input"))
      (node (ref "R14") (pin "2") (pinfunction "2_2") (pintype "input"))
    )
    (net (code "63") (name "Net-(LED4-Pad1)") (class "Default")
      (node (ref "LED4") (pin "1") (pinfunction "1_1") (pintype "input"))
      (node (ref "R15") (pin "2") (pinfunction "2_2") (pintype "input"))
    )
    (net (code "64") (name "Net-(LED5-Pad1)") (class "Default")
      (node (ref "LED5") (pin "1") (pinfunction "1_1") (pintype "input"))
      (node (ref "R16") (pin "2") (pinfunction "2_2") (pintype "input"))
    )
    (net (code "65") (name "Net-(Q1-B)") (class "Default")
      (node (ref "Q1") (pin "2") (pinfunction "B_2") (pintype "input"))
      (node (ref "R2") (pin "2") (pinfunction "2_2") (pintype "input"))
    )
    (net (code "66") (name "Net-(U4-V3)") (class "Default")
      (node (ref "C6") (pin "1") (pinfunction "1_1") (pintype "input"))
      (node (ref "U4") (pin "4") (pinfunction "V3_4") (pintype "input"))
    )
    (net (code "67") (name "VCC") (class "Default")
      (node (ref "C7") (pin "2") (pinfunction "2_2") (pintype "input"))
      (node (ref "SW1") (pin "2") (pinfunction "2_2") (pintype "input"))
      (node (ref "U4") (pin "16") (pinfunction "VCC_16") (pintype "input"))
      (node (ref "USB1") (pin "1") (pinfunction "VCC_1") (pintype "input"))
    )
    (net (code "68") (name "unconnected-(SW1-Pad1)") (class "Default")
      (node (ref "SW1") (pin "1") (pinfunction "1_1") (pintype "input+no_connect"))
    )
    (net (code "69") (name "unconnected-(U1-NC-Pad3)") (class "Default")
      (node (ref "U1") (pin "3") (pinfunction "NC_3") (pintype "input+no_connect"))
    )
    (net (code "70") (name "unconnected-(U3-NC-Pad10)") (class "Default")
      (node (ref "U3") (pin "10") (pinfunction "NC_10") (pintype "input+no_connect"))
    )
    (net (code "71") (name "unconnected-(U3-NC-Pad13)") (class "Default")
      (node (ref "U3") (pin "13") (pinfunction "NC_13") (pintype "input+no_connect"))
    )
    (net (code "72") (name "unconnected-(U3-Q7&apos;-Pad9)") (class "Default")
      (node (ref "U3") (pin "9") (pinfunction "Q7&apos;_9") (pintype "input+no_connect"))
    )
    (net (code "73") (name "unconnected-(U4-CTS#-Pad9)") (class "Default")
      (node (ref "U4") (pin "9") (pinfunction "CTS#_9") (pintype "input+no_connect"))
    )
    (net (code "74") (name "unconnected-(U4-DCD#-Pad12)") (class "Default")
      (node (ref "U4") (pin "12") (pinfunction "DCD#_12") (pintype "input+no_connect"))
    )
    (net (code "75") (name "unconnected-(U4-DSR#-Pad10)") (class "Default")
      (node (ref "U4") (pin "10") (pinfunction "DSR#_10") (pintype "input+no_connect"))
    )
    (net (code "76") (name "unconnected-(U4-DTR#-Pad13)") (class "Default")
      (node (ref "U4") (pin "13") (pinfunction "DTR#_13") (pintype "input+no_connect"))
    )
    (net (code "77") (name "unconnected-(U4-NC.-Pad7)") (class "Default")
      (node (ref "U4") (pin "7") (pinfunction "NC._7") (pintype "input+no_connect"))
    )
    (net (code "78") (name "unconnected-(U4-NC.-Pad8)") (class "Default")
      (node (ref "U4") (pin "8") (pinfunction "NC._8") (pintype "input+no_connect"))
    )
    (net (code "79") (name "unconnected-(U4-R232-Pad15)") (class "Default")
      (node (ref "U4") (pin "15") (pinfunction "R232_15") (pintype "input+no_connect"))
    )
    (net (code "80") (name "unconnected-(U4-RI#-Pad11)") (class "Default")
      (node (ref "U4") (pin "11") (pinfunction "RI#_11") (pintype "input+no_connect"))
    )
    (net (code "81") (name "unconnected-(U4-RTS#-Pad14)") (class "Default")
      (node (ref "U4") (pin "14") (pinfunction "RTS#_14") (pintype "input+no_connect"))
    )
    (net (code "82") (name "unconnected-(USB1-ID-Pad4)") (class "Default")
      (node (ref "USB1") (pin "4") (pinfunction "ID_4") (pintype "input+no_connect"))
    )
  )
)
